# Shooter.net
KiCad netlist of a schematic drawn in Altium Designer
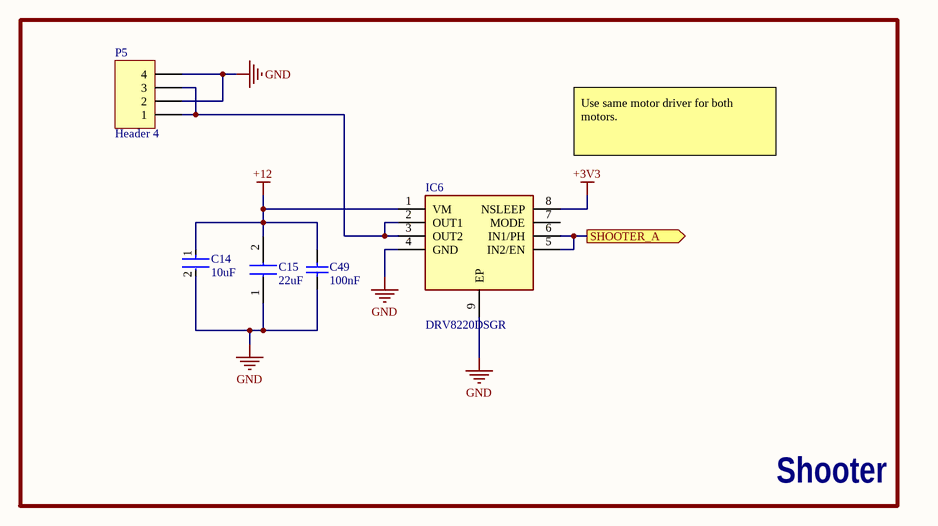
[diagram p0: Shooter.SchDoc]

(export (version "E")
  (design (tool "Eeschema 10.0.6"))
  (components
    (comp (ref "C14")
      (value "CL05A106MP5NUNC")
      (footprint "FP-CL05A106MP5NUNC-MFG")
      (description "CAP CER 10UF 10V X5R 0402")
      (fields
        (field (name "OCTOPART") "https://octopart.com/cl05a106mp5nunc-samsung-22457395")
        (field (name "TOLERANCE") "20%")
        (field (name "CAPACITANCE") "10uF")
      )
      (libsource (lib "Altium Content Vault") (part "b4654b650e69147ec39a6b967a45e02"))
    )
    (comp (ref "C15")
      (value "22uF")
      (footprint "SamacSys:CAPC1608X105N")
      (description "Capacitor")
      (fields
        (field (name "MANUFACTURER_PART_NUMBER") "CL10A226MP8NUNE")
        (field (name "MOUSER PART NUMBER") "187-CL10A226MP8NUNE")
      )
      (libsource (lib "*") (part "CL10A226MP8NUNE"))
    )
    (comp (ref "C49")
      (value "CL05B104KO5NNNC")
      (footprint "CAPC1050X55X23ML05T13")
      (description "Chip Capacitor, 100 nF, +/- 10%, 16 V, -55 to 125 degC, 0402 (1005 Metric), RoHS, Tape and Reel")
      (fields (field (name "MANUFACTURER") "Samsung Electro-Mechanics") (field (name "CAPACITANCE") "100nF"))
      (libsource (lib "Altium Content Vault") (part "CAP-NP-2"))
    )
    (comp (ref "IC6")
      (value "DRV8220DSGR")
      (footprint "SamacSys:SON50P200X200X80-9N")
      (description "Integrated Circuit")
      (fields (field (name "MOUSER PART NUMBER") "595-DRV8220DSGR"))
      (libsource (lib "SamacSys") (part "DRV8220DSGR"))
    )
    (comp (ref "P5")
      (value "Header 4")
      (footprint "HDR1X4")
      (description "Header, 4-Pin")
      (fields (field (name "PUBLISHER") "Altium Limited"))
      (libsource (lib "Miscellaneous Connectors") (part "Header 4"))
    )
  )
  (nets
    (net (code "1") (name "+3V3") (class "Default")
      (node (ref "IC6") (pin "8") (pinfunction "NSLEEP_8") (pintype "passive"))
    )
    (net (code "2") (name "+12") (class "Default")
      (node (ref "C14") (pin "1") (pinfunction "1_1") (pintype "passive"))
      (node (ref "C15") (pin "2") (pinfunction "2_2") (pintype "passive"))
      (node (ref "C49") (pin "2") (pinfunction "2_2") (pintype "passive"))
      (node (ref "IC6") (pin "1") (pinfunction "VM_1") (pintype "passive"))
    )
    (net (code "3") (name "/SHOOTER_A") (class "Default")
      (node (ref "IC6") (pin "5") (pinfunction "IN2/EN_5") (pintype "passive"))
      (node (ref "IC6") (pin "6") (pinfunction "IN1/PH_6") (pintype "passive"))
    )
    (net (code "4") (name "GND") (class "Default")
      (node (ref "C14") (pin "2") (pinfunction "2_2") (pintype "passive"))
      (node (ref "C15") (pin "1") (pinfunction "1_1") (pintype "passive"))
      (node (ref "C49") (pin "1") (pinfunction "1_1") (pintype "passive"))
      (node (ref "IC6") (pin "4") (pinfunction "GND_4") (pintype "passive"))
      (node (ref "IC6") (pin "9") (pinfunction "EP_9") (pintype "passive"))
      (node (ref "P5") (pin "2") (pinfunction "2_2") (pintype "passive"))
      (node (ref "P5") (pin "4") (pinfunction "4_4") (pintype "passive"))
    )
    (net (code "5") (name "Net-(IC6-OUT1)") (class "Default")
      (node (ref "IC6") (pin "2") (pinfunction "OUT1_2") (pintype "passive"))
      (node (ref "IC6") (pin "3") (pinfunction "OUT2_3") (pintype "passive"))
      (node (ref "P5") (pin "1") (pinfunction "1_1") (pintype "passive"))
      (node (ref "P5") (pin "3") (pinfunction "3_3") (pintype "passive"))
    )
    (net (code "6") (name "unconnected-(IC6-MODE-Pad7)") (class "Default")
      (node (ref "IC6") (pin "7") (pinfunction "MODE_7") (pintype "passive"))
    )
  )
)
